# SCH_GroeiAcademie-v0_10_0_2026-07-25.net
KiCad netlist of a schematic drawn in EasyEDA
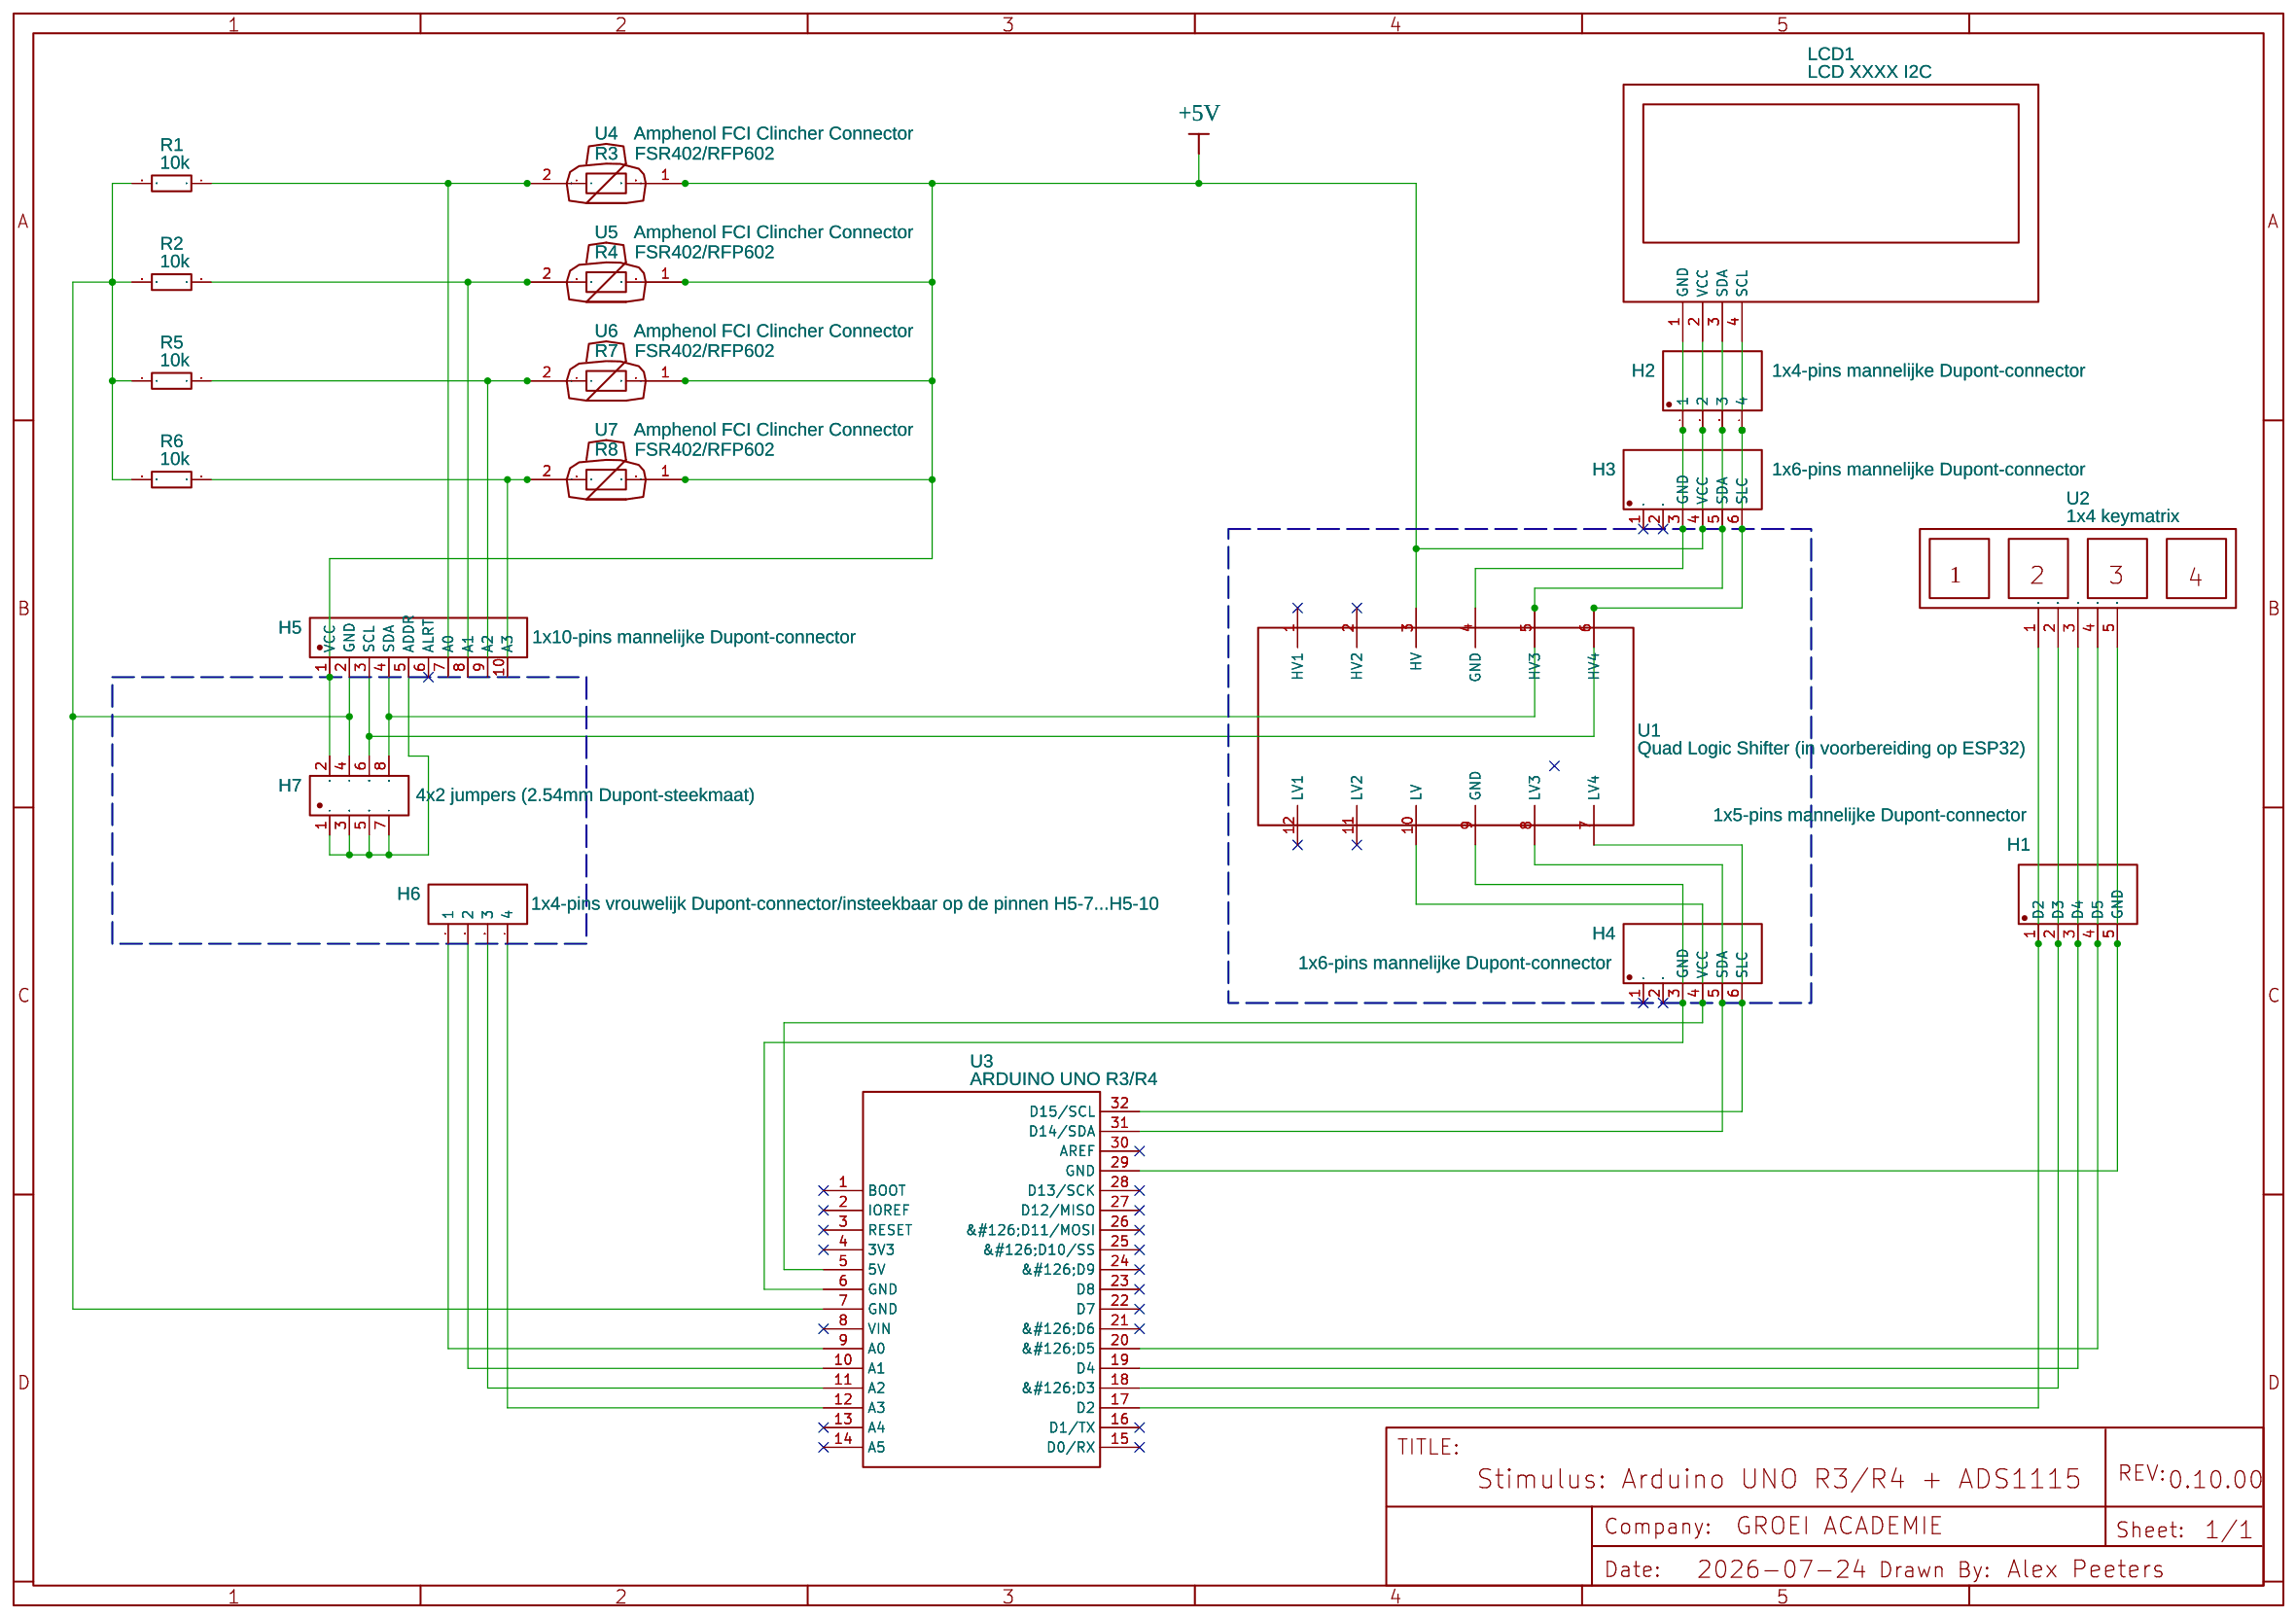
[diagram p0: schematic sheet]

(export (version "E")
  (design (tool "Eeschema 10.0.6"))
  (components
    (comp (ref "H1")
      (value "1x5-pins mannelijke Dupont-connector")
      (fields (field (name "Manufacturer Part") "B-2100S05P-A110") (field (name "Manufacturer") "Ckmtw(灿科盟)"))
      (libsource (lib "") (part "210S-1*5P L=11.6MMGold-plated black"))
    )
    (comp (ref "H2")
      (value "1x4-pins mannelijke Dupont-connector")
      (fields (field (name "Manufacturer Part") "B-2100S04P-A110") (field (name "Manufacturer") "Ckmtw(灿科盟)"))
      (libsource (lib "") (part "Header-Male-2.54_1x4"))
    )
    (comp (ref "H3")
      (value "1x6-pins mannelijke Dupont-connector")
      (fields (field (name "Manufacturer Part") "B-2100S06P-A110") (field (name "Manufacturer") "Ckmtw(灿科盟)"))
      (libsource (lib "") (part "210S-1*6P L=11.6MMGold-plated black"))
    )
    (comp (ref "H4")
      (value "1x6-pins mannelijke Dupont-connector")
      (fields (field (name "Manufacturer Part") "B-2100S06P-A110") (field (name "Manufacturer") "Ckmtw(灿科盟)"))
      (libsource (lib "") (part "210S-1*6P L=11.6MMGold-plated black"))
    )
    (comp (ref "H5")
      (value "1x10-pins mannelijke Dupont-connector")
      (fields (field (name "Manufacturer Part") "2.54-1*10") (field (name "Manufacturer") "ZHOURI(洲日)"))
      (libsource (lib "") (part "2.54-1*10"))
    )
    (comp (ref "H6")
      (value "1x4-pins vrouwelijk Dupont-connector/insteekbaar op de pinnen H5-7...H5-10")
      (libsource (lib "") (part "HDR-2.54_1x4"))
    )
    (comp (ref "H7")
      (value "4x2 jumpers (2.54mm Dupont-steekmaat)")
      (fields (field (name "Manufacturer Part") "2.54-2*4P立贴针") (field (name "Manufacturer") "BOOMELE(博穆精密)"))
      (libsource (lib "") (part "2.54-2*4P立贴针"))
    )
    (comp (ref "LCD1") (value "LCD XXXX I2C") (libsource (lib "") (part "I2CLCD16X2_N")))
    (comp (ref "R1")
      (value "10k")
      (fields (field (name "Manufacturer") "Made in China"))
      (libsource (lib "") (part "330Ω (331) ±5%"))
    )
    (comp (ref "R2")
      (value "10k")
      (fields (field (name "Manufacturer") "Made in China"))
      (libsource (lib "") (part "330Ω (331) ±5%"))
    )
    (comp (ref "R3") (value "FSR402/RFP602") (libsource (lib "") (part "FSR402-OPCION1")))
    (comp (ref "R4") (value "FSR402/RFP602") (libsource (lib "") (part "FSR402-OPCION1")))
    (comp (ref "R5")
      (value "10k")
      (fields (field (name "Manufacturer") "Made in China"))
      (libsource (lib "") (part "330Ω (331) ±5%"))
    )
    (comp (ref "R6")
      (value "10k")
      (fields (field (name "Manufacturer") "Made in China"))
      (libsource (lib "") (part "330Ω (331) ±5%"))
    )
    (comp (ref "R7") (value "FSR402/RFP602") (libsource (lib "") (part "FSR402-OPCION1")))
    (comp (ref "R8") (value "FSR402/RFP602") (libsource (lib "") (part "FSR402-OPCION1")))
    (comp (ref "U1")
      (value "Quad Logic Shifter (in voorbereiding op ESP32)")
      (libsource (lib "") (part "Quad Logic Shifter"))
    )
    (comp (ref "U2") (value "1x4 keymatrix") (libsource (lib "") (part "Клавиатура 4*4")))
    (comp (ref "U3") (value "ARDUINO UNO R3/R4") (libsource (lib "") (part "ARDUINO UNO R4 MINIMA")))
    (comp (ref "U4")
      (value "Amphenol FCI Clincher Connector")
      (fields (field (name "Manufacturer Part") "AT04-2P-BM02") (field (name "Manufacturer") "Amphenol"))
      (libsource (lib "") (part "AT04-2P"))
    )
    (comp (ref "U5")
      (value "Amphenol FCI Clincher Connector")
      (fields (field (name "Manufacturer Part") "AT04-2P-BM02") (field (name "Manufacturer") "Amphenol"))
      (libsource (lib "") (part "AT04-2P"))
    )
    (comp (ref "U6")
      (value "Amphenol FCI Clincher Connector")
      (fields (field (name "Manufacturer Part") "AT04-2P-BM02") (field (name "Manufacturer") "Amphenol"))
      (libsource (lib "") (part "AT04-2P"))
    )
    (comp (ref "U7")
      (value "Amphenol FCI Clincher Connector")
      (fields (field (name "Manufacturer Part") "AT04-2P-BM02") (field (name "Manufacturer") "Amphenol"))
      (libsource (lib "") (part "AT04-2P"))
    )
  )
  (nets
    (net (code "1") (name "+5V") (class "Default")
      (node (ref "H2") (pin "2") (pinfunction "2_2") (pintype "unspecified"))
      (node (ref "H3") (pin "4") (pinfunction "VCC_4") (pintype "unspecified"))
      (node (ref "H5") (pin "1") (pinfunction "VCC_1") (pintype "unspecified"))
      (node (ref "H7") (pin "2") (pinfunction "2_2") (pintype "unspecified"))
      (node (ref "LCD1") (pin "2") (pinfunction "VCC_2") (pintype "unspecified"))
      (node (ref "R3") (pin "2") (pinfunction "2_2") (pintype "unspecified"))
      (node (ref "R4") (pin "2") (pinfunction "2_2") (pintype "unspecified"))
      (node (ref "R7") (pin "2") (pinfunction "2_2") (pintype "unspecified"))
      (node (ref "R8") (pin "2") (pinfunction "2_2") (pintype "unspecified"))
      (node (ref "U1") (pin "3") (pinfunction "HV_3") (pintype "unspecified"))
      (node (ref "U4") (pin "1") (pinfunction "1_1") (pintype "unspecified"))
      (node (ref "U5") (pin "1") (pinfunction "1_1") (pintype "unspecified"))
      (node (ref "U6") (pin "1") (pinfunction "1_1") (pintype "unspecified"))
      (node (ref "U7") (pin "1") (pinfunction "1_1") (pintype "unspecified"))
    )
    (net (code "2") (name "Net-(H1-D2)") (class "Default")
      (node (ref "H1") (pin "1") (pinfunction "D2_1") (pintype "unspecified"))
      (node (ref "U2") (pin "1") (pinfunction "C1_1") (pintype "unspecified"))
      (node (ref "U3") (pin "17") (pinfunction "D2_17") (pintype "unspecified"))
    )
    (net (code "3") (name "Net-(H1-D3)") (class "Default")
      (node (ref "H1") (pin "2") (pinfunction "D3_2") (pintype "unspecified"))
      (node (ref "U2") (pin "2") (pinfunction "C2_2") (pintype "unspecified"))
      (node (ref "U3") (pin "18") (pinfunction "&#126;D3_18") (pintype "unspecified"))
    )
    (net (code "4") (name "Net-(H1-D4)") (class "Default")
      (node (ref "H1") (pin "3") (pinfunction "D4_3") (pintype "unspecified"))
      (node (ref "U2") (pin "3") (pinfunction "C3_3") (pintype "unspecified"))
      (node (ref "U3") (pin "19") (pinfunction "D4_19") (pintype "unspecified"))
    )
    (net (code "5") (name "Net-(H1-D5)") (class "Default")
      (node (ref "H1") (pin "4") (pinfunction "D5_4") (pintype "unspecified"))
      (node (ref "U2") (pin "4") (pinfunction "R1_4") (pintype "unspecified"))
      (node (ref "U3") (pin "20") (pinfunction "&#126;D5_20") (pintype "unspecified"))
    )
    (net (code "6") (name "Net-(H1-GND)") (class "Default")
      (node (ref "H1") (pin "5") (pinfunction "GND_5") (pintype "unspecified"))
      (node (ref "U2") (pin "5") (pinfunction "R2_5") (pintype "unspecified"))
      (node (ref "U3") (pin "29") (pinfunction "GND_29") (pintype "unspecified"))
    )
    (net (code "7") (name "Net-(H3-GND)") (class "Default")
      (node (ref "H2") (pin "1") (pinfunction "1_1") (pintype "unspecified"))
      (node (ref "H3") (pin "3") (pinfunction "GND_3") (pintype "unspecified"))
      (node (ref "LCD1") (pin "1") (pinfunction "GND_1") (pintype "unspecified"))
      (node (ref "U1") (pin "4") (pinfunction "GND_4") (pintype "unspecified"))
    )
    (net (code "8") (name "Net-(H3-SDA)") (class "Default")
      (node (ref "H2") (pin "3") (pinfunction "3_3") (pintype "unspecified"))
      (node (ref "H3") (pin "5") (pinfunction "SDA_5") (pintype "unspecified"))
      (node (ref "H5") (pin "4") (pinfunction "SDA_4") (pintype "unspecified"))
      (node (ref "H7") (pin "8") (pinfunction "8_8") (pintype "unspecified"))
      (node (ref "LCD1") (pin "3") (pinfunction "SDA_3") (pintype "unspecified"))
      (node (ref "U1") (pin "5") (pinfunction "HV3_5") (pintype "unspecified"))
    )
    (net (code "9") (name "Net-(H3-SLC)") (class "Default")
      (node (ref "H2") (pin "4") (pinfunction "4_4") (pintype "unspecified"))
      (node (ref "H3") (pin "6") (pinfunction "SLC_6") (pintype "unspecified"))
      (node (ref "H5") (pin "3") (pinfunction "SCL_3") (pintype "unspecified"))
      (node (ref "H7") (pin "6") (pinfunction "6_6") (pintype "unspecified"))
      (node (ref "LCD1") (pin "4") (pinfunction "SCL_4") (pintype "unspecified"))
      (node (ref "U1") (pin "6") (pinfunction "HV4_6") (pintype "unspecified"))
    )
    (net (code "10") (name "Net-(H4-GND)") (class "Default")
      (node (ref "H4") (pin "3") (pinfunction "GND_3") (pintype "unspecified"))
      (node (ref "U1") (pin "9") (pinfunction "GND_9") (pintype "unspecified"))
      (node (ref "U3") (pin "6") (pinfunction "GND_6") (pintype "unspecified"))
    )
    (net (code "11") (name "Net-(H4-SDA)") (class "Default")
      (node (ref "H4") (pin "5") (pinfunction "SDA_5") (pintype "unspecified"))
      (node (ref "U1") (pin "8") (pinfunction "LV3_8") (pintype "unspecified"))
      (node (ref "U3") (pin "31") (pinfunction "D14/SDA_31") (pintype "unspecified"))
    )
    (net (code "12") (name "Net-(H4-SLC)") (class "Default")
      (node (ref "H4") (pin "6") (pinfunction "SLC_6") (pintype "unspecified"))
      (node (ref "U1") (pin "7") (pinfunction "LV4_7") (pintype "unspecified"))
      (node (ref "U3") (pin "32") (pinfunction "D15/SCL_32") (pintype "unspecified"))
    )
    (net (code "13") (name "Net-(H4-VCC)") (class "Default")
      (node (ref "H4") (pin "4") (pinfunction "VCC_4") (pintype "unspecified"))
      (node (ref "U1") (pin "10") (pinfunction "LV_10") (pintype "unspecified"))
      (node (ref "U3") (pin "5") (pinfunction "5V_5") (pintype "unspecified"))
    )
    (net (code "14") (name "Net-(H5-A0)") (class "Default")
      (node (ref "H5") (pin "7") (pinfunction "A0_7") (pintype "unspecified"))
      (node (ref "R1") (pin "1") (pinfunction "1_1") (pintype "unspecified"))
      (node (ref "R3") (pin "1") (pinfunction "1_1") (pintype "unspecified"))
      (node (ref "U4") (pin "2") (pinfunction "2_2") (pintype "unspecified"))
    )
    (net (code "15") (name "Net-(H5-A1)") (class "Default")
      (node (ref "H5") (pin "8") (pinfunction "A1_8") (pintype "unspecified"))
      (node (ref "R2") (pin "1") (pinfunction "1_1") (pintype "unspecified"))
      (node (ref "R4") (pin "1") (pinfunction "1_1") (pintype "unspecified"))
      (node (ref "U5") (pin "2") (pinfunction "2_2") (pintype "unspecified"))
    )
    (net (code "16") (name "Net-(H5-A2)") (class "Default")
      (node (ref "H5") (pin "9") (pinfunction "A2_9") (pintype "unspecified"))
      (node (ref "R5") (pin "1") (pinfunction "1_1") (pintype "unspecified"))
      (node (ref "R7") (pin "1") (pinfunction "1_1") (pintype "unspecified"))
      (node (ref "U6") (pin "2") (pinfunction "2_2") (pintype "unspecified"))
    )
    (net (code "17") (name "Net-(H5-A3)") (class "Default")
      (node (ref "H5") (pin "10") (pinfunction "A3_10") (pintype "unspecified"))
      (node (ref "R6") (pin "1") (pinfunction "1_1") (pintype "unspecified"))
      (node (ref "R8") (pin "1") (pinfunction "1_1") (pintype "unspecified"))
      (node (ref "U7") (pin "2") (pinfunction "2_2") (pintype "unspecified"))
    )
    (net (code "18") (name "Net-(H5-ADDR)") (class "Default")
      (node (ref "H5") (pin "5") (pinfunction "ADDR_5") (pintype "unspecified"))
      (node (ref "H7") (pin "1") (pinfunction "1_1") (pintype "unspecified"))
      (node (ref "H7") (pin "3") (pinfunction "3_3") (pintype "unspecified"))
      (node (ref "H7") (pin "5") (pinfunction "5_5") (pintype "unspecified"))
      (node (ref "H7") (pin "7") (pinfunction "7_7") (pintype "unspecified"))
    )
    (net (code "19") (name "Net-(H5-GND)") (class "Default")
      (node (ref "H5") (pin "2") (pinfunction "GND_2") (pintype "unspecified"))
      (node (ref "H7") (pin "4") (pinfunction "4_4") (pintype "unspecified"))
      (node (ref "R1") (pin "2") (pinfunction "2_2") (pintype "unspecified"))
      (node (ref "R2") (pin "2") (pinfunction "2_2") (pintype "unspecified"))
      (node (ref "R5") (pin "2") (pinfunction "2_2") (pintype "unspecified"))
      (node (ref "R6") (pin "2") (pinfunction "2_2") (pintype "unspecified"))
      (node (ref "U3") (pin "7") (pinfunction "GND_7") (pintype "unspecified"))
    )
    (net (code "20") (name "Net-(U3-A0)") (class "Default")
      (node (ref "H6") (pin "1") (pinfunction "1_1") (pintype "unspecified"))
      (node (ref "U3") (pin "9") (pinfunction "A0_9") (pintype "unspecified"))
    )
    (net (code "21") (name "Net-(U3-A1)") (class "Default")
      (node (ref "H6") (pin "2") (pinfunction "2_2") (pintype "unspecified"))
      (node (ref "U3") (pin "10") (pinfunction "A1_10") (pintype "unspecified"))
    )
    (net (code "22") (name "Net-(U3-A2)") (class "Default")
      (node (ref "H6") (pin "3") (pinfunction "3_3") (pintype "unspecified"))
      (node (ref "U3") (pin "11") (pinfunction "A2_11") (pintype "unspecified"))
    )
    (net (code "23") (name "Net-(U3-A3)") (class "Default")
      (node (ref "H6") (pin "4") (pinfunction "4_4") (pintype "unspecified"))
      (node (ref "U3") (pin "12") (pinfunction "A3_12") (pintype "unspecified"))
    )
    (net (code "24") (name "unconnected-(H3-Pad1)") (class "Default")
      (node (ref "H3") (pin "1") (pinfunction "1_1") (pintype "unspecified+no_connect"))
    )
    (net (code "25") (name "unconnected-(H3-Pad2)") (class "Default")
      (node (ref "H3") (pin "2") (pinfunction "2_2") (pintype "unspecified+no_connect"))
    )
    (net (code "26") (name "unconnected-(H4-Pad1)") (class "Default")
      (node (ref "H4") (pin "1") (pinfunction "1_1") (pintype "unspecified+no_connect"))
    )
    (net (code "27") (name "unconnected-(H4-Pad2)") (class "Default")
      (node (ref "H4") (pin "2") (pinfunction "2_2") (pintype "unspecified+no_connect"))
    )
    (net (code "28") (name "unconnected-(H5-ALRT-Pad6)") (class "Default")
      (node (ref "H5") (pin "6") (pinfunction "ALRT_6") (pintype "unspecified+no_connect"))
    )
    (net (code "29") (name "unconnected-(U1-HV1-Pad1)") (class "Default")
      (node (ref "U1") (pin "1") (pinfunction "HV1_1") (pintype "unspecified+no_connect"))
    )
    (net (code "30") (name "unconnected-(U1-HV2-Pad2)") (class "Default")
      (node (ref "U1") (pin "2") (pinfunction "HV2_2") (pintype "unspecified+no_connect"))
    )
    (net (code "31") (name "unconnected-(U1-LV1-Pad12)") (class "Default")
      (node (ref "U1") (pin "12") (pinfunction "LV1_12") (pintype "unspecified+no_connect"))
    )
    (net (code "32") (name "unconnected-(U1-LV2-Pad11)") (class "Default")
      (node (ref "U1") (pin "11") (pinfunction "LV2_11") (pintype "unspecified+no_connect"))
    )
    (net (code "33") (name "unconnected-(U3-&#126;D6-Pad21)") (class "Default")
      (node (ref "U3") (pin "21") (pinfunction "&#126;D6_21") (pintype "unspecified+no_connect"))
    )
    (net (code "34") (name "unconnected-(U3-&#126;D9-Pad24)") (class "Default")
      (node (ref "U3") (pin "24") (pinfunction "&#126;D9_24") (pintype "unspecified+no_connect"))
    )
    (net (code "35") (name "unconnected-(U3-&#126;D10{slash}SS-Pad25)") (class "Default")
      (node (ref "U3") (pin "25") (pinfunction "&#126;D10/SS_25") (pintype "unspecified+no_connect"))
    )
    (net (code "36") (name "unconnected-(U3-&#126;D11{slash}MOSI-Pad26)") (class "Default")
      (node (ref "U3") (pin "26") (pinfunction "&#126;D11/MOSI_26") (pintype "unspecified+no_connect"))
    )
    (net (code "37") (name "unconnected-(U3-3V3-Pad4)") (class "Default")
      (node (ref "U3") (pin "4") (pinfunction "3V3_4") (pintype "unspecified+no_connect"))
    )
    (net (code "38") (name "unconnected-(U3-A4-Pad13)") (class "Default")
      (node (ref "U3") (pin "13") (pinfunction "A4_13") (pintype "unspecified+no_connect"))
    )
    (net (code "39") (name "unconnected-(U3-A5-Pad14)") (class "Default")
      (node (ref "U3") (pin "14") (pinfunction "A5_14") (pintype "unspecified+no_connect"))
    )
    (net (code "40") (name "unconnected-(U3-AREF-Pad30)") (class "Default")
      (node (ref "U3") (pin "30") (pinfunction "AREF_30") (pintype "unspecified+no_connect"))
    )
    (net (code "41") (name "unconnected-(U3-BOOT-Pad1)") (class "Default")
      (node (ref "U3") (pin "1") (pinfunction "BOOT_1") (pintype "unspecified+no_connect"))
    )
    (net (code "42") (name "unconnected-(U3-D0{slash}RX-Pad15)") (class "Default")
      (node (ref "U3") (pin "15") (pinfunction "D0/RX_15") (pintype "unspecified+no_connect"))
    )
    (net (code "43") (name "unconnected-(U3-D1{slash}TX-Pad16)") (class "Default")
      (node (ref "U3") (pin "16") (pinfunction "D1/TX_16") (pintype "unspecified+no_connect"))
    )
    (net (code "44") (name "unconnected-(U3-D7-Pad22)") (class "Default")
      (node (ref "U3") (pin "22") (pinfunction "D7_22") (pintype "unspecified+no_connect"))
    )
    (net (code "45") (name "unconnected-(U3-D8-Pad23)") (class "Default")
      (node (ref "U3") (pin "23") (pinfunction "D8_23") (pintype "unspecified+no_connect"))
    )
    (net (code "46") (name "unconnected-(U3-D12{slash}MISO-Pad27)") (class "Default")
      (node (ref "U3") (pin "27") (pinfunction "D12/MISO_27") (pintype "unspecified+no_connect"))
    )
    (net (code "47") (name "unconnected-(U3-D13{slash}SCK-Pad28)") (class "Default")
      (node (ref "U3") (pin "28") (pinfunction "D13/SCK_28") (pintype "unspecified+no_connect"))
    )
    (net (code "48") (name "unconnected-(U3-IOREF-Pad2)") (class "Default")
      (node (ref "U3") (pin "2") (pinfunction "IOREF_2") (pintype "unspecified+no_connect"))
    )
    (net (code "49") (name "unconnected-(U3-RESET-Pad3)") (class "Default")
      (node (ref "U3") (pin "3") (pinfunction "RESET_3") (pintype "unspecified+no_connect"))
    )
    (net (code "50") (name "unconnected-(U3-VIN-Pad8)") (class "Default")
      (node (ref "U3") (pin "8") (pinfunction "VIN_8") (pintype "unspecified+no_connect"))
    )
  )
)
